# Schematic.net
KiCad netlist of a schematic drawn in EAGLE
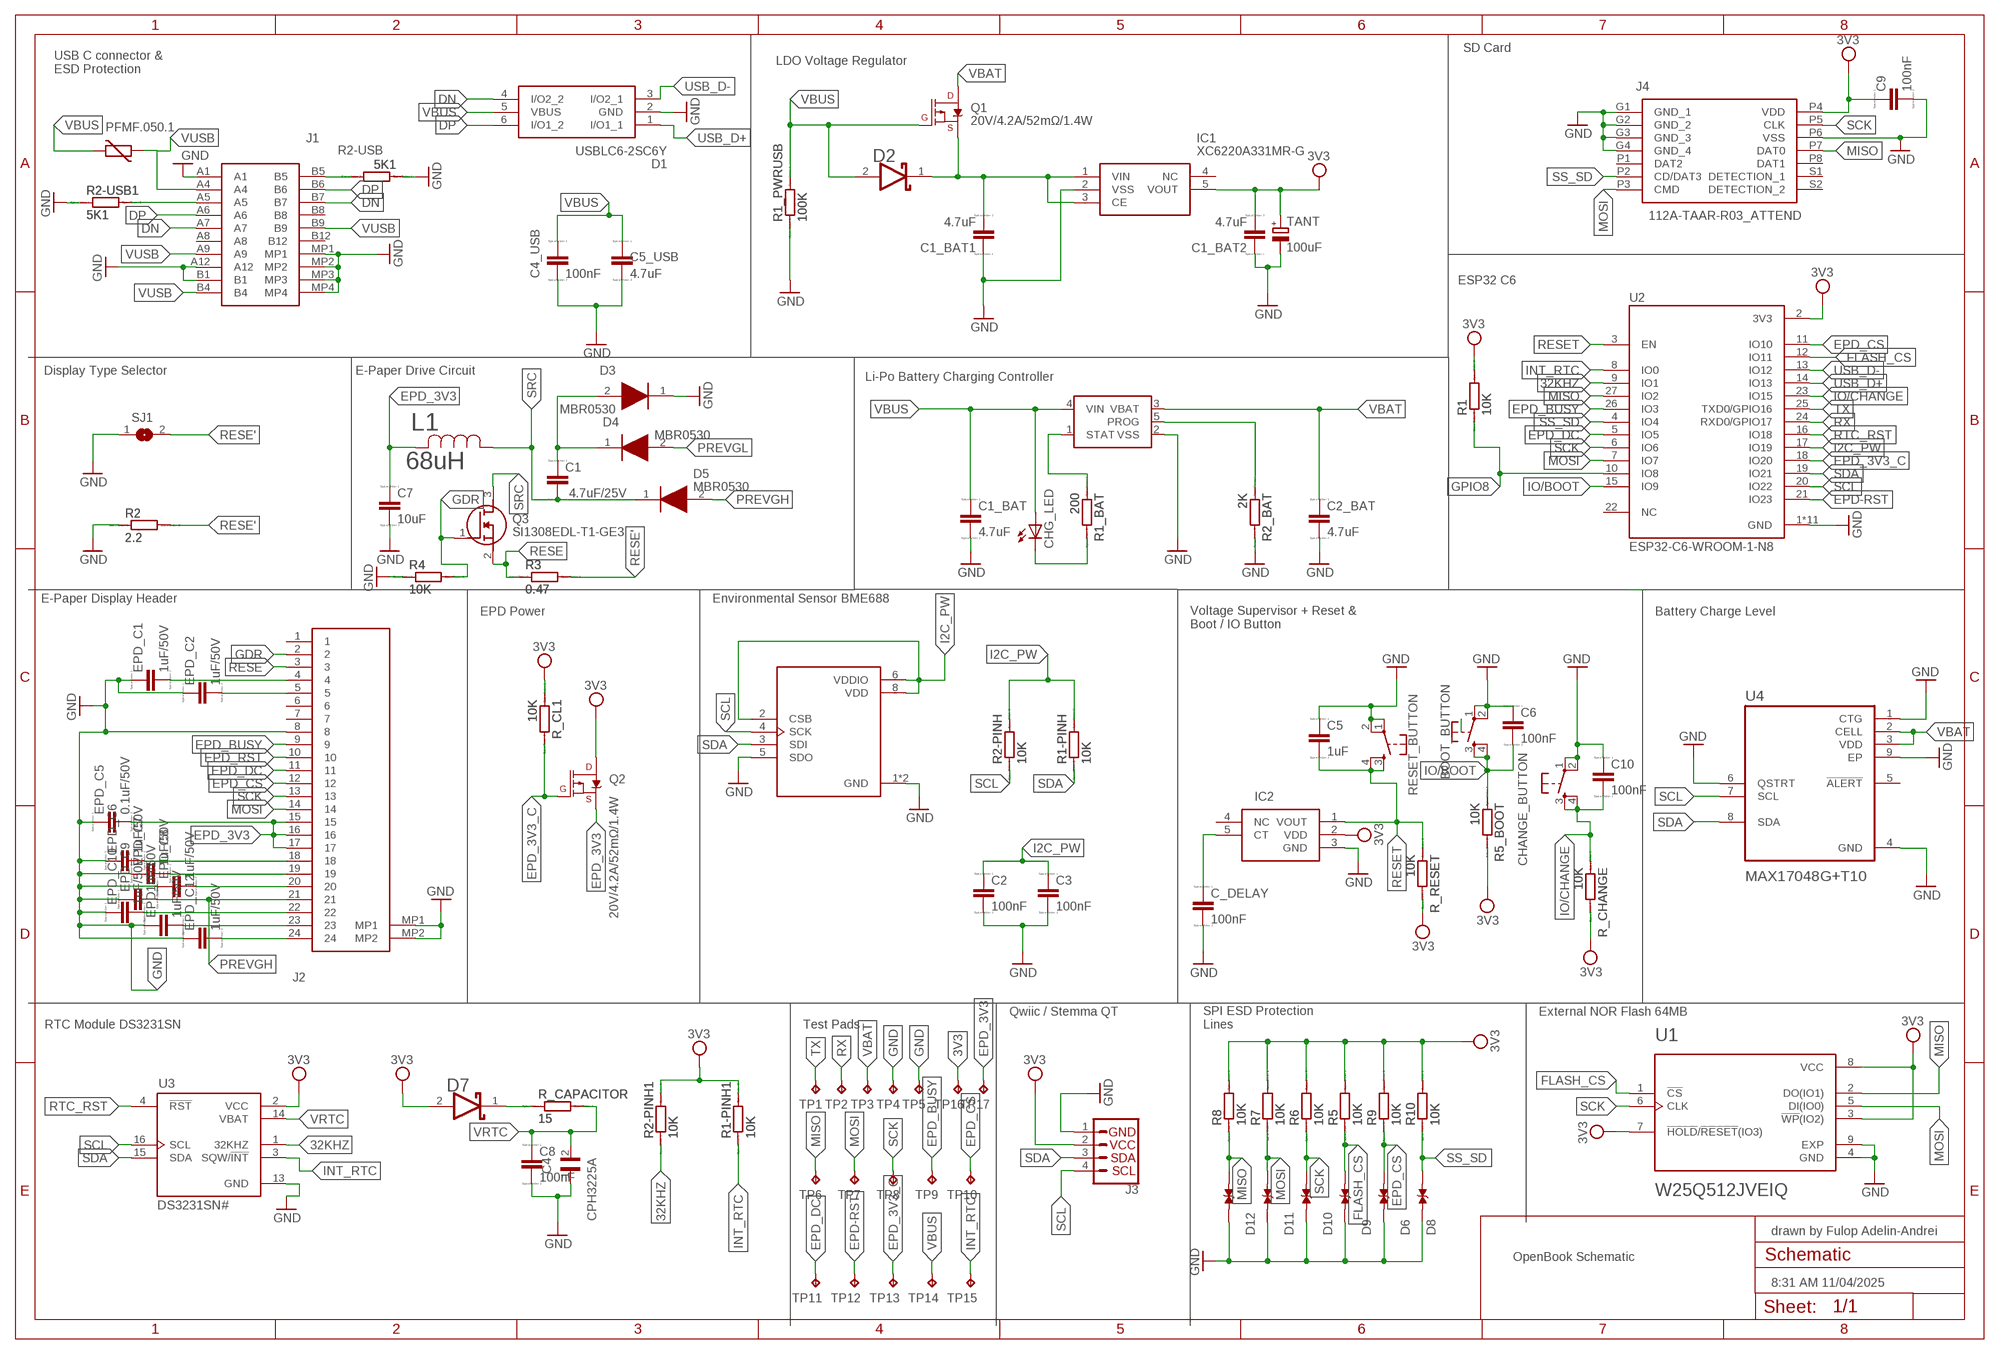
[diagram p0: schematic, sheet 1]

(export (version "E")
  (design (tool "Eeschema 10.0.6"))
  (components
    (comp (ref "BOOT_BUTTON")
      (value "BUTTON_CUSYOMV1")
      (footprint "eagle-import:MYBUTTON")
      (libsource (lib "eagle-import") (part "BUTTON_CUSYOMV1"))
    )
    (comp (ref "C1")
      (value "4.7uF/25V")
      (footprint "eagle-import:EAGLE-LTSPICE_C0402")
      (libsource (lib "eagle-import") (part "EAGLE-LTSPICE_CC0402"))
    )
    (comp (ref "C1_BAT")
      (value "4.7uF")
      (footprint "eagle-import:EAGLE-LTSPICE_C0402")
      (libsource (lib "eagle-import") (part "EAGLE-LTSPICE_CC0402"))
    )
    (comp (ref "C1_BAT1")
      (value "4.7uF")
      (footprint "eagle-import:ESP32_WROVER_EAGLE-LTSPICE_C0402")
      (libsource (lib "eagle-import") (part "ESP32_WROVER_EAGLE-LTSPICE_CC0402"))
    )
    (comp (ref "C1_BAT2")
      (value "4.7uF")
      (footprint "eagle-import:ESP32_WROVER_EAGLE-LTSPICE_C0402")
      (libsource (lib "eagle-import") (part "ESP32_WROVER_EAGLE-LTSPICE_CC0402"))
    )
    (comp (ref "C2")
      (value "100nF")
      (footprint "eagle-import:ESP32_WROVER_EAGLE-LTSPICE_C0402")
      (libsource (lib "eagle-import") (part "ESP32_WROVER_EAGLE-LTSPICE_CC0402"))
    )
    (comp (ref "C2_BAT")
      (value "4.7uF")
      (footprint "eagle-import:EAGLE-LTSPICE_C0402")
      (libsource (lib "eagle-import") (part "EAGLE-LTSPICE_CC0402"))
    )
    (comp (ref "C3")
      (value "100nF")
      (footprint "eagle-import:ESP32_WROVER_EAGLE-LTSPICE_C0402")
      (libsource (lib "eagle-import") (part "ESP32_WROVER_EAGLE-LTSPICE_CC0402"))
    )
    (comp (ref "C4")
      (value "CPH3225A")
      (footprint "eagle-import:CAPCP3225X100N")
      (fields (field (name "MF") "Seiko Instruments"))
      (libsource (lib "eagle-import") (part "CPH3225A"))
    )
    (comp (ref "C4_USB")
      (value "100nF")
      (footprint "eagle-import:EAGLE-LTSPICE_C0402")
      (libsource (lib "eagle-import") (part "EAGLE-LTSPICE_CC0402"))
    )
    (comp (ref "C5")
      (value "1uF")
      (footprint "eagle-import:ESP32_WROVER_EAGLE-LTSPICE_C0402")
      (libsource (lib "eagle-import") (part "ESP32_WROVER_EAGLE-LTSPICE_CC0402"))
    )
    (comp (ref "C5_USB")
      (value "4.7uF")
      (footprint "eagle-import:EAGLE-LTSPICE_C0402")
      (libsource (lib "eagle-import") (part "EAGLE-LTSPICE_CC0402"))
    )
    (comp (ref "C6")
      (value "100nF")
      (footprint "eagle-import:ESP32_WROVER_EAGLE-LTSPICE_C0402")
      (libsource (lib "eagle-import") (part "ESP32_WROVER_EAGLE-LTSPICE_CC0402"))
    )
    (comp (ref "C7")
      (value "10uF")
      (footprint "eagle-import:EAGLE-LTSPICE_C0402")
      (libsource (lib "eagle-import") (part "EAGLE-LTSPICE_CC0402"))
    )
    (comp (ref "C8")
      (value "100nF")
      (footprint "eagle-import:ESP32_WROVER_EAGLE-LTSPICE_C0402")
      (libsource (lib "eagle-import") (part "ESP32_WROVER_EAGLE-LTSPICE_CC0402"))
    )
    (comp (ref "C9")
      (value "100nF")
      (footprint "eagle-import:EAGLE-LTSPICE_C0402")
      (libsource (lib "eagle-import") (part "EAGLE-LTSPICE_CC0402"))
    )
    (comp (ref "C10")
      (value "100nF")
      (footprint "eagle-import:ESP32_WROVER_EAGLE-LTSPICE_C0402")
      (libsource (lib "eagle-import") (part "ESP32_WROVER_EAGLE-LTSPICE_CC0402"))
    )
    (comp (ref "CHANGE_BUTTON")
      (value "BUTTON_CUSYOMV1")
      (footprint "eagle-import:MYBUTTON")
      (libsource (lib "eagle-import") (part "BUTTON_CUSYOMV1"))
    )
    (comp (ref "CHG_LED")
      (value "ADAFRUIT_LEDCHIP-LED0603")
      (footprint "eagle-import:ADAFRUIT_CHIP-LED0603")
      (libsource (lib "eagle-import") (part "ADAFRUIT_LEDCHIP-LED0603"))
    )
    (comp (ref "C_DELAY")
      (value "100nF")
      (footprint "eagle-import:EAGLE-LTSPICE_C0402")
      (libsource (lib "eagle-import") (part "EAGLE-LTSPICE_CC0402"))
    )
    (comp (ref "D1")
      (value "USBLC6-2SC6Y")
      (footprint "eagle-import:SOT95P280X145-6N")
      (fields (field (name "MF") "STMicroelectronics"))
      (libsource (lib "eagle-import") (part "USBLC6-2SC6Y"))
    )
    (comp (ref "D2")
      (value "ESP32_WROVER_AVX---SD0805S020S1R0_AVX_SD0805S020S1R0_0_0AVX_SD0805S020S1R0_0_0")
      (footprint "eagle-import:ESP32_WROVER_AVX---SD0805S020S1R0_AVX_SD0805S020S1R0_0")
      (fields
        (field (name "DIGIKEY_PART_NUMBER") "478-7800-1-ND")
        (field (name "MF") "AVX")
        (field (name "MOUSER_PART_NUMBER") "581-SD0805S020S1R0")
      )
      (libsource (lib "eagle-import") (part "ESP32_WROVER_AVX---SD0805S020S1R0_AVX_SD0805S020S1R0_0_0AVX_SD0805S020S1R0_0_0"))
    )
    (comp (ref "D3")
      (value "MBR0530")
      (footprint "eagle-import:SOD3716X135N")
      (fields (field (name "MF") "ON Semiconductor"))
      (libsource (lib "eagle-import") (part "MBR0530"))
    )
    (comp (ref "D4")
      (value "MBR0530")
      (footprint "eagle-import:SOD3716X135N")
      (fields (field (name "MF") "ON Semiconductor"))
      (libsource (lib "eagle-import") (part "MBR0530"))
    )
    (comp (ref "D5")
      (value "MBR0530")
      (footprint "eagle-import:SOD3716X135N")
      (fields (field (name "MF") "ON Semiconductor"))
      (libsource (lib "eagle-import") (part "MBR0530"))
    )
    (comp (ref "D6")
      (value "PGB1010603MR")
      (footprint "eagle-import:DIOC1608X36N")
      (fields (field (name "MF") "Littelfuse Inc."))
      (libsource (lib "eagle-import") (part "PGB1010603MR"))
    )
    (comp (ref "D7")
      (value "ESP32_WROVER_AVX---SD0805S020S1R0_AVX_SD0805S020S1R0_0_0AVX_SD0805S020S1R0_0_0")
      (footprint "eagle-import:ESP32_WROVER_AVX---SD0805S020S1R0_AVX_SD0805S020S1R0_0")
      (fields
        (field (name "DIGIKEY_PART_NUMBER") "478-7800-1-ND")
        (field (name "MF") "AVX")
        (field (name "MOUSER_PART_NUMBER") "581-SD0805S020S1R0")
      )
      (libsource (lib "eagle-import") (part "ESP32_WROVER_AVX---SD0805S020S1R0_AVX_SD0805S020S1R0_0_0AVX_SD0805S020S1R0_0_0"))
    )
    (comp (ref "D8")
      (value "PGB1010603MR")
      (footprint "eagle-import:DIOC1608X36N")
      (fields (field (name "MF") "Littelfuse Inc."))
      (libsource (lib "eagle-import") (part "PGB1010603MR"))
    )
    (comp (ref "D9")
      (value "PGB1010603MR")
      (footprint "eagle-import:DIOC1608X36N")
      (fields (field (name "MF") "Littelfuse Inc."))
      (libsource (lib "eagle-import") (part "PGB1010603MR"))
    )
    (comp (ref "D10")
      (value "PGB1010603MR")
      (footprint "eagle-import:DIOC1608X36N")
      (fields (field (name "MF") "Littelfuse Inc."))
      (libsource (lib "eagle-import") (part "PGB1010603MR"))
    )
    (comp (ref "D11")
      (value "PGB1010603MR")
      (footprint "eagle-import:DIOC1608X36N")
      (fields (field (name "MF") "Littelfuse Inc."))
      (libsource (lib "eagle-import") (part "PGB1010603MR"))
    )
    (comp (ref "D12")
      (value "PGB1010603MR")
      (footprint "eagle-import:DIOC1608X36N")
      (fields (field (name "MF") "Littelfuse Inc."))
      (libsource (lib "eagle-import") (part "PGB1010603MR"))
    )
    (comp (ref "EPD_C1")
      (value "1uF/50V")
      (footprint "eagle-import:EAGLE-LTSPICE_C0402")
      (libsource (lib "eagle-import") (part "EAGLE-LTSPICE_CC0402"))
    )
    (comp (ref "EPD_C2")
      (value "1uF/50V")
      (footprint "eagle-import:EAGLE-LTSPICE_C0402")
      (libsource (lib "eagle-import") (part "EAGLE-LTSPICE_CC0402"))
    )
    (comp (ref "EPD_C5")
      (value "0.1uF/50V")
      (footprint "eagle-import:EAGLE-LTSPICE_C0402")
      (libsource (lib "eagle-import") (part "EAGLE-LTSPICE_CC0402"))
    )
    (comp (ref "EPD_C6")
      (value "1uF/50V")
      (footprint "eagle-import:EAGLE-LTSPICE_C0402")
      (libsource (lib "eagle-import") (part "EAGLE-LTSPICE_CC0402"))
    )
    (comp (ref "EPD_C7")
      (value "1uF/50V")
      (footprint "eagle-import:EAGLE-LTSPICE_C0402")
      (libsource (lib "eagle-import") (part "EAGLE-LTSPICE_CC0402"))
    )
    (comp (ref "EPD_C8")
      (value "1uF/50V")
      (footprint "eagle-import:EAGLE-LTSPICE_C0402")
      (libsource (lib "eagle-import") (part "EAGLE-LTSPICE_CC0402"))
    )
    (comp (ref "EPD_C9")
      (value "1uF/50V")
      (footprint "eagle-import:EAGLE-LTSPICE_C0402")
      (libsource (lib "eagle-import") (part "EAGLE-LTSPICE_CC0402"))
    )
    (comp (ref "EPD_C10")
      (value "1uF/50V")
      (footprint "eagle-import:EAGLE-LTSPICE_C0402")
      (libsource (lib "eagle-import") (part "EAGLE-LTSPICE_CC0402"))
    )
    (comp (ref "EPD_C11")
      (value "1uF/50V")
      (footprint "eagle-import:EAGLE-LTSPICE_C0402")
      (libsource (lib "eagle-import") (part "EAGLE-LTSPICE_CC0402"))
    )
    (comp (ref "EPD_C12")
      (value "1uF/50V")
      (footprint "eagle-import:EAGLE-LTSPICE_C0402")
      (libsource (lib "eagle-import") (part "EAGLE-LTSPICE_CC0402"))
    )
    (comp (ref "IC1")
      (value "XC6220A331MR-G")
      (footprint "eagle-import:SOT95P280X120-5N")
      (fields (field (name "MOUSER_PART_NUMBER") "865-XC6220A331MR-G"))
      (libsource (lib "eagle-import") (part "XC6220A331MR-G"))
    )
    (comp (ref "IC2")
      (value "BD5229G-TR")
      (footprint "eagle-import:SOT95P280X125-5N")
      (fields (field (name "MOUSER_PART_NUMBER") "755-BD5229G-TR"))
      (libsource (lib "eagle-import") (part "BD5229G-TR"))
    )
    (comp (ref "J1")
      (value "SAMACSYS_PARTS_USB4110-GF-A")
      (footprint "eagle-import:SAMACSYS_PARTS_USB4110GFA")
      (fields
        (field (name "MANUFACTURER_PART_NUMBER") "USB4110-GF-A")
        (field (name "MOUSER_PART_NUMBER") "640-USB4110-GF-A")
      )
      (libsource (lib "eagle-import") (part "SAMACSYS_PARTS_USB4110-GF-A"))
    )
    (comp (ref "J2")
      (value "FH34SRJ-24S-0.5SH_99_")
      (footprint "eagle-import:FH34SRJ24S05SH99")
      (fields
        (field (name "MANUFACTURER_PART_NUMBER") "FH34SRJ-24S-0.5SH(99)")
        (field (name "MOUSER_PART_NUMBER") "798-FH34SRJ24S05SH99")
      )
      (libsource (lib "eagle-import") (part "FH34SRJ-24S-0.5SH_99_"))
    )
    (comp (ref "J3")
      (value "QWIIC_RIGHT_ANGLE")
      (footprint "eagle-import:JST04_1MM_RA")
      (libsource (lib "eagle-import") (part "QWIIC_CONNECTORJS-1MM"))
    )
    (comp (ref "J4")
      (value "112A-TAAR-R03_ATTEND")
      (footprint "eagle-import:112ATAARR03ATTEND")
      (fields (field (name "MANUFACTURER_PART_NUMBER") "112A-TAAR-R03 ATTEND"))
      (libsource (lib "eagle-import") (part "112A-TAAR-R03_ATTEND"))
    )
    (comp (ref "L1")
      (value "68uH")
      (footprint "eagle-import:IND_4828-WE-TPC_WRE")
      (fields
        (field (name "MANUFACTURER_PART_NUMBER") "744043680")
        (field (name "COPYRIGHT") "Copyright (C) 2024 Ultra Librarian. All rights reserved.")
      )
      (libsource (lib "eagle-import") (part "744043680IND_4828-WE-TPC_WRE"))
    )
    (comp (ref "PFMF.050.1")
      (value "ESP32C6_VARISTORCN1812")
      (footprint "eagle-import:ESP32C6_VARISTOR_CT_CN1812")
      (libsource (lib "eagle-import") (part "ESP32C6_VARISTORCN1812"))
    )
    (comp (ref "Q1")
      (value "20V/4.2A/52mΩ/1.4W")
      (footprint "eagle-import:ESP32_WROVER_SPARKFUN-DISCRETESEMI_SOT23-3")
      (libsource (lib "eagle-import") (part "ESP32_WROVER_SPARKFUN-DISCRETESEMI_MOSFET_PCH-DMG2305UX-7"))
    )
    (comp (ref "Q2")
      (value "20V/4.2A/52mΩ/1.4W")
      (footprint "eagle-import:ESP32_WROVER_SPARKFUN-DISCRETESEMI_SOT23-3")
      (libsource (lib "eagle-import") (part "ESP32_WROVER_SPARKFUN-DISCRETESEMI_MOSFET_PCH-DMG2305UX-7"))
    )
    (comp (ref "Q3")
      (value "SI1308EDL-T1-GE3")
      (footprint "eagle-import:SOT65P210X110-3N")
      (fields (field (name "MF") "Vishay Siliconix"))
      (libsource (lib "eagle-import") (part "SI1308EDL-T1-GE3"))
    )
    (comp (ref "R1")
      (value "10K")
      (footprint "eagle-import:ESP32_WROVER_EAGLE-LTSPICE_R0402")
      (libsource (lib "eagle-import") (part "ESP32_WROVER_EAGLE-LTSPICE_RR0402"))
    )
    (comp (ref "R1-PINH")
      (value "10K")
      (footprint "eagle-import:ESP32_WROVER_EAGLE-LTSPICE_R0402")
      (libsource (lib "eagle-import") (part "ESP32_WROVER_EAGLE-LTSPICE_RR0402"))
    )
    (comp (ref "R1-PINH1")
      (value "10K")
      (footprint "eagle-import:ESP32_WROVER_EAGLE-LTSPICE_R0402")
      (libsource (lib "eagle-import") (part "ESP32_WROVER_EAGLE-LTSPICE_RR0402"))
    )
    (comp (ref "R1_BAT")
      (value "200")
      (footprint "eagle-import:ESP32_WROVER_EAGLE-LTSPICE_R0402")
      (libsource (lib "eagle-import") (part "ESP32_WROVER_EAGLE-LTSPICE_RR0402"))
    )
    (comp (ref "R1_PWRUSB")
      (value "100K")
      (footprint "eagle-import:ESP32_WROVER_EAGLE-LTSPICE_R0402")
      (libsource (lib "eagle-import") (part "ESP32_WROVER_EAGLE-LTSPICE_RR0402"))
    )
    (comp (ref "R2")
      (value "2.2")
      (footprint "eagle-import:ESP32_WROVER_EAGLE-LTSPICE_R0402")
      (libsource (lib "eagle-import") (part "ESP32_WROVER_EAGLE-LTSPICE_RR0402"))
    )
    (comp (ref "R2-PINH")
      (value "10K")
      (footprint "eagle-import:ESP32_WROVER_EAGLE-LTSPICE_R0402")
      (libsource (lib "eagle-import") (part "ESP32_WROVER_EAGLE-LTSPICE_RR0402"))
    )
    (comp (ref "R2-PINH1")
      (value "10K")
      (footprint "eagle-import:ESP32_WROVER_EAGLE-LTSPICE_R0402")
      (libsource (lib "eagle-import") (part "ESP32_WROVER_EAGLE-LTSPICE_RR0402"))
    )
    (comp (ref "R2-USB")
      (value "5K1")
      (footprint "eagle-import:ESP32_WROVER_EAGLE-LTSPICE_R0402")
      (libsource (lib "eagle-import") (part "ESP32_WROVER_EAGLE-LTSPICE_RR0402"))
    )
    (comp (ref "R2-USB1")
      (value "5K1")
      (footprint "eagle-import:ESP32_WROVER_EAGLE-LTSPICE_R0402")
      (libsource (lib "eagle-import") (part "ESP32_WROVER_EAGLE-LTSPICE_RR0402"))
    )
    (comp (ref "R2_BAT")
      (value "2K")
      (footprint "eagle-import:ESP32_WROVER_EAGLE-LTSPICE_R0402")
      (libsource (lib "eagle-import") (part "ESP32_WROVER_EAGLE-LTSPICE_RR0402"))
    )
    (comp (ref "R3")
      (value "0.47")
      (footprint "eagle-import:ESP32_WROVER_EAGLE-LTSPICE_R0402")
      (libsource (lib "eagle-import") (part "ESP32_WROVER_EAGLE-LTSPICE_RR0402"))
    )
    (comp (ref "R4")
      (value "10K")
      (footprint "eagle-import:ESP32_WROVER_EAGLE-LTSPICE_R0402")
      (libsource (lib "eagle-import") (part "ESP32_WROVER_EAGLE-LTSPICE_RR0402"))
    )
    (comp (ref "R5")
      (value "10K")
      (footprint "eagle-import:ESP32_WROVER_EAGLE-LTSPICE_R0402")
      (libsource (lib "eagle-import") (part "ESP32_WROVER_EAGLE-LTSPICE_RR0402"))
    )
    (comp (ref "R5_BOOT")
      (value "10K")
      (footprint "eagle-import:ESP32_WROVER_EAGLE-LTSPICE_R0402")
      (libsource (lib "eagle-import") (part "ESP32_WROVER_EAGLE-LTSPICE_RR0402"))
    )
    (comp (ref "R6")
      (value "10K")
      (footprint "eagle-import:ESP32_WROVER_EAGLE-LTSPICE_R0402")
      (libsource (lib "eagle-import") (part "ESP32_WROVER_EAGLE-LTSPICE_RR0402"))
    )
    (comp (ref "R7")
      (value "10K")
      (footprint "eagle-import:ESP32_WROVER_EAGLE-LTSPICE_R0402")
      (libsource (lib "eagle-import") (part "ESP32_WROVER_EAGLE-LTSPICE_RR0402"))
    )
    (comp (ref "R8")
      (value "10K")
      (footprint "eagle-import:ESP32_WROVER_EAGLE-LTSPICE_R0402")
      (libsource (lib "eagle-import") (part "ESP32_WROVER_EAGLE-LTSPICE_RR0402"))
    )
    (comp (ref "R9")
      (value "10K")
      (footprint "eagle-import:ESP32_WROVER_EAGLE-LTSPICE_R0402")
      (libsource (lib "eagle-import") (part "ESP32_WROVER_EAGLE-LTSPICE_RR0402"))
    )
    (comp (ref "R10")
      (value "10K")
      (footprint "eagle-import:ESP32_WROVER_EAGLE-LTSPICE_R0402")
      (libsource (lib "eagle-import") (part "ESP32_WROVER_EAGLE-LTSPICE_RR0402"))
    )
    (comp (ref "RESET_BUTTON")
      (value "BUTTON_CUSYOMV1")
      (footprint "eagle-import:MYBUTTON")
      (libsource (lib "eagle-import") (part "BUTTON_CUSYOMV1"))
    )
    (comp (ref "R_CAPACITOR")
      (value "15")
      (footprint "eagle-import:ESP32_WROVER_EAGLE-LTSPICE_R0402")
      (libsource (lib "eagle-import") (part "ESP32_WROVER_EAGLE-LTSPICE_RR0402"))
    )
    (comp (ref "R_CHANGE")
      (value "10K")
      (footprint "eagle-import:ESP32_WROVER_EAGLE-LTSPICE_R0402")
      (libsource (lib "eagle-import") (part "ESP32_WROVER_EAGLE-LTSPICE_RR0402"))
    )
    (comp (ref "R_CL1")
      (value "10K")
      (footprint "eagle-import:ESP32_WROVER_EAGLE-LTSPICE_R0402")
      (libsource (lib "eagle-import") (part "ESP32_WROVER_EAGLE-LTSPICE_RR0402"))
    )
    (comp (ref "R_RESET")
      (value "10K")
      (footprint "eagle-import:ESP32_WROVER_EAGLE-LTSPICE_R0402")
      (libsource (lib "eagle-import") (part "ESP32_WROVER_EAGLE-LTSPICE_RR0402"))
    )
    (comp (ref "SJ1") (value "SJ") (footprint "eagle-import:SJ") (libsource (lib "eagle-import") (part "SJ")))
    (comp (ref "TANT")
      (value "100uF")
      (footprint "eagle-import:RCL_CT3528")
      (libsource (lib "eagle-import") (part "RCL_CPOL-EUCT3528"))
    )
    (comp (ref "TP1")
      (value "TPTP20R")
      (footprint "eagle-import:TP20R")
      (libsource (lib "eagle-import") (part "TPTP20R"))
    )
    (comp (ref "TP2")
      (value "TPTP20R")
      (footprint "eagle-import:TP20R")
      (libsource (lib "eagle-import") (part "TPTP20R"))
    )
    (comp (ref "TP3")
      (value "TPTP20R")
      (footprint "eagle-import:TP20R")
      (libsource (lib "eagle-import") (part "TPTP20R"))
    )
    (comp (ref "TP4")
      (value "TPTP20R")
      (footprint "eagle-import:TP20R")
      (libsource (lib "eagle-import") (part "TPTP20R"))
    )
    (comp (ref "TP5")
      (value "TPTP20R")
      (footprint "eagle-import:TP20R")
      (libsource (lib "eagle-import") (part "TPTP20R"))
    )
    (comp (ref "TP6")
      (value "TPTP20R")
      (footprint "eagle-import:TP20R")
      (libsource (lib "eagle-import") (part "TPTP20R"))
    )
    (comp (ref "TP7")
      (value "TPTP20R")
      (footprint "eagle-import:TP20R")
      (libsource (lib "eagle-import") (part "TPTP20R"))
    )
    (comp (ref "TP8")
      (value "TPTP20R")
      (footprint "eagle-import:TP20R")
      (libsource (lib "eagle-import") (part "TPTP20R"))
    )
    (comp (ref "TP9")
      (value "TPTP20R")
      (footprint "eagle-import:TP20R")
      (libsource (lib "eagle-import") (part "TPTP20R"))
    )
    (comp (ref "TP10")
      (value "TPTP20R")
      (footprint "eagle-import:TP20R")
      (libsource (lib "eagle-import") (part "TPTP20R"))
    )
    (comp (ref "TP11")
      (value "TPTP20R")
      (footprint "eagle-import:TP20R")
      (libsource (lib "eagle-import") (part "TPTP20R"))
    )
    (comp (ref "TP12")
      (value "TPTP20R")
      (footprint "eagle-import:TP20R")
      (libsource (lib "eagle-import") (part "TPTP20R"))
    )
    (comp (ref "TP13")
      (value "TPTP20R")
      (footprint "eagle-import:TP20R")
      (libsource (lib "eagle-import") (part "TPTP20R"))
    )
    (comp (ref "TP14")
      (value "TPTP20R")
      (footprint "eagle-import:TP20R")
      (libsource (lib "eagle-import") (part "TPTP20R"))
    )
    (comp (ref "TP15")
      (value "TPTP20R")
      (footprint "eagle-import:TP20R")
      (libsource (lib "eagle-import") (part "TPTP20R"))
    )
    (comp (ref "TP16")
      (value "TPTP20R")
      (footprint "eagle-import:TP20R")
      (libsource (lib "eagle-import") (part "TPTP20R"))
    )
    (comp (ref "TP17")
      (value "TPTP20R")
      (footprint "eagle-import:TP20R")
      (libsource (lib "eagle-import") (part "TPTP20R"))
    )
    (comp (ref "U1")
      (value "W25Q512JVEIQ")
      (footprint "eagle-import:SON127P600X800X80-9N")
      (fields (field (name "MF") "Winbond Electronics"))
      (libsource (lib "eagle-import") (part "W25Q512JVEIQ"))
    )
    (comp (ref "U2")
      (value "ESP32-C6-WROOM-1-N8")
      (footprint "eagle-import:XCVR_ESP32-C6-WROOM-1-N8")
      (fields (field (name "MF") "Espressif Systems"))
      (libsource (lib "eagle-import") (part "ESP32-C6-WROOM-1-N8"))
    )
    (comp (ref "U3")
      (value "DS3231SN#")
      (footprint "eagle-import:SOIC127P1032X265-16N")
      (fields (field (name "MF") "Analog Devices"))
      (libsource (lib "eagle-import") (part "DS3231SN#"))
    )
    (comp (ref "U4")
      (value "MAX17048G+T10")
      (footprint "eagle-import:SON50P200X200X80-9N")
      (fields (field (name "MF") "Analog Devices"))
      (libsource (lib "eagle-import") (part "MAX17048G+T10"))
    )
    (comp (ref "U9")
      (value "ESP32_WROVER_SPARKFUN-IC-POWER_MCP73831")
      (footprint "eagle-import:ESP32_WROVER_SPARKFUN-IC-POWER_SOT23-5")
      (libsource (lib "eagle-import") (part "ESP32_WROVER_SPARKFUN-IC-POWER_MCP73831"))
    )
    (comp (ref "U10")
      (value "ESP32_WROVER_BME680_BME680")
      (footprint "eagle-import:ESP32_WROVER_BME680_PSON80P300X300X100-8N")
      (fields (field (name "MF") "Bosch Sensortec") (field (name "MP") "BME680"))
      (libsource (lib "eagle-import") (part "ESP32_WROVER_BME680_BME680"))
    )
  )
  (nets
    (net (code "1") (name "3V3") (class "Default")
      (node (ref "C1_BAT2") (pin "2") (pinfunction "2_2") (pintype "passive"))
      (node (ref "C9") (pin "1") (pinfunction "1_1") (pintype "passive"))
      (node (ref "D7") (pin "2") (pinfunction "ANODE_2") (pintype "bidirectional"))
      (node (ref "IC1") (pin "5") (pinfunction "VOUT_5") (pintype "bidirectional"))
      (node (ref "IC2") (pin "2") (pinfunction "VDD_2") (pintype "bidirectional"))
      (node (ref "J3") (pin "2") (pinfunction "2_2") (pintype "power_in"))
      (node (ref "J4") (pin "P4") (pinfunction "VDD_P4") (pintype "bidirectional"))
      (node (ref "Q2") (pin "3") (pinfunction "D_3") (pintype "bidirectional"))
      (node (ref "R1") (pin "2") (pinfunction "2_2") (pintype "passive"))
      (node (ref "R1-PINH1") (pin "2") (pinfunction "2_2") (pintype "passive"))
      (node (ref "R10") (pin "2") (pinfunction "2_2") (pintype "passive"))
      (node (ref "R2-PINH1") (pin "2") (pinfunction "2_2") (pintype "passive"))
      (node (ref "R5") (pin "2") (pinfunction "2_2") (pintype "passive"))
      (node (ref "R5_BOOT") (pin "2") (pinfunction "2_2") (pintype "passive"))
      (node (ref "R6") (pin "2") (pinfunction "2_2") (pintype "passive"))
      (node (ref "R7") (pin "2") (pinfunction "2_2") (pintype "passive"))
      (node (ref "R8") (pin "2") (pinfunction "2_2") (pintype "passive"))
      (node (ref "R9") (pin "2") (pinfunction "2_2") (pintype "passive"))
      (node (ref "R_CHANGE") (pin "2") (pinfunction "2_2") (pintype "passive"))
      (node (ref "R_CL1") (pin "1") (pinfunction "1_1") (pintype "passive"))
      (node (ref "R_RESET") (pin "2") (pinfunction "2_2") (pintype "passive"))
      (node (ref "TANT") (pin "+") (pinfunction "+_+") (pintype "passive"))
      (node (ref "TP16") (pin "TP") (pinfunction "TP_TP") (pintype "input"))
      (node (ref "U1") (pin "3") (pinfunction "~{WP}(IO2)_3") (pintype "bidirectional"))
      (node (ref "U1") (pin "7") (pinfunction "~{HOLD}/~{RESET}(IO3)_7") (pintype "bidirectional"))
      (node (ref "U1") (pin "8") (pinfunction "VCC_8") (pintype "power_in"))
      (node (ref "U2") (pin "2") (pinfunction "3V3_2") (pintype "power_in"))
      (node (ref "U3") (pin "2") (pinfunction "VCC_2") (pintype "power_in"))
    )
    (net (code "2") (name "32KHZ") (class "Default")
      (node (ref "R2-PINH1") (pin "1") (pinfunction "1_1") (pintype "passive"))
      (node (ref "U2") (pin "9") (pinfunction "IO1_9") (pintype "bidirectional"))
      (node (ref "U3") (pin "1") (pinfunction "32KHZ_1") (pintype "output"))
    )
    (net (code "3") (name "DN") (class "Default")
      (node (ref "D1") (pin "4") (pinfunction "I/O2_2_4") (pintype "bidirectional"))
      (node (ref "J1") (pin "A7") (pinfunction "A7_A7") (pintype "bidirectional"))
      (node (ref "J1") (pin "B7") (pinfunction "B7_B7") (pintype "bidirectional"))
    )
    (net (code "4") (name "DP") (class "Default")
      (node (ref "D1") (pin "6") (pinfunction "I/O1_2_6") (pintype "bidirectional"))
      (node (ref "J1") (pin "A6") (pinfunction "A6_A6") (pintype "bidirectional"))
      (node (ref "J1") (pin "B6") (pinfunction "B6_B6") (pintype "bidirectional"))
    )
    (net (code "5") (name "EPD-RST") (class "Default")
      (node (ref "TP12") (pin "TP") (pinfunction "TP_TP") (pintype "input"))
      (node (ref "U2") (pin "21") (pinfunction "IO23_21") (pintype "bidirectional"))
    )
    (net (code "6") (name "EPD_3V3") (class "Default")
      (node (ref "C7") (pin "1") (pinfunction "1_1") (pintype "passive"))
      (node (ref "EPD_C5") (pin "2") (pinfunction "2_2") (pintype "passive"))
      (node (ref "J2") (pin "15") (pinfunction "15_15") (pintype "bidirectional"))
      (node (ref "J2") (pin "16") (pinfunction "16_16") (pintype "bidirectional"))
      (node (ref "J2") (pin "17") (pinfunction "17_17") (pintype "bidirectional"))
      (node (ref "L1") (pin "2") (pinfunction "2_2") (pintype "passive"))
      (node (ref "Q2") (pin "2") (pinfunction "S_2") (pintype "bidirectional"))
      (node (ref "TP17") (pin "TP") (pinfunction "TP_TP") (pintype "input"))
    )
    (net (code "7") (name "EPD_3V3_C") (class "Default")
      (node (ref "Q2") (pin "1") (pinfunction "G_1") (pintype "bidirectional"))
      (node (ref "R_CL1") (pin "2") (pinfunction "2_2") (pintype "passive"))
      (node (ref "TP13") (pin "TP") (pinfunction "TP_TP") (pintype "input"))
      (node (ref "U2") (pin "18") (pinfunction "IO20_18") (pintype "bidirectional"))
    )
    (net (code "8") (name "EPD_BUSY") (class "Default")
      (node (ref "J2") (pin "9") (pinfunction "9_9") (pintype "bidirectional"))
      (node (ref "TP9") (pin "TP") (pinfunction "TP_TP") (pintype "input"))
      (node (ref "U2") (pin "26") (pinfunction "IO3_26") (pintype "bidirectional"))
    )
    (net (code "9") (name "EPD_CS") (class "Default")
      (node (ref "D6") (pin "2") (pinfunction "2_2") (pintype "passive"))
      (node (ref "J2") (pin "12") (pinfunction "12_12") (pintype "bidirectional"))
      (node (ref "R9") (pin "1") (pinfunction "1_1") (pintype "passive"))
      (node (ref "TP10") (pin "TP") (pinfunction "TP_TP") (pintype "input"))
      (node (ref "U2") (pin "11") (pinfunction "IO10_11") (pintype "bidirectional"))
    )
    (net (code "10") (name "EPD_DC") (class "Default")
      (node (ref "J2") (pin "11") (pinfunction "11_11") (pintype "bidirectional"))
      (node (ref "TP11") (pin "TP") (pinfunction "TP_TP") (pintype "input"))
      (node (ref "U2") (pin "5") (pinfunction "IO5_5") (pintype "bidirectional"))
    )
    (net (code "11") (name "EPD_RST") (class "Default")
      (node (ref "J2") (pin "10") (pinfunction "10_10") (pintype "bidirectional"))
    )
    (net (code "12") (name "FLASH_CS") (class "Default")
      (node (ref "D9") (pin "2") (pinfunction "2_2") (pintype "passive"))
      (node (ref "R5") (pin "1") (pinfunction "1_1") (pintype "passive"))
      (node (ref "U1") (pin "1") (pinfunction "~{CS}_1") (pintype "input"))
      (node (ref "U2") (pin "12") (pinfunction "IO11_12") (pintype "bidirectional"))
    )
    (net (code "13") (name "GDR") (class "Default")
      (node (ref "J2") (pin "2") (pinfunction "2_2") (pintype "bidirectional"))
      (node (ref "Q3") (pin "1") (pinfunction "G_1") (pintype "bidirectional"))
      (node (ref "R4") (pin "2") (pinfunction "2_2") (pintype "passive"))
    )
    (net (code "14") (name "GND") (class "Default")
      (node (ref "BOOT_BUTTON") (pin "1") (pinfunction "1_1") (pintype "passive"))
      (node (ref "BOOT_BUTTON") (pin "2") (pinfunction "2_2") (pintype "passive"))
      (node (ref "C10") (pin "1") (pinfunction "1_1") (pintype "passive"))
      (node (ref "C1_BAT") (pin "2") (pinfunction "2_2") (pintype "passive"))
      (node (ref "C1_BAT1") (pin "1") (pinfunction "1_1") (pintype "passive"))
      (node (ref "C1_BAT2") (pin "1") (pinfunction "1_1") (pintype "passive"))
      (node (ref "C2") (pin "2") (pinfunction "2_2") (pintype "passive"))
      (node (ref "C2_BAT") (pin "2") (pinfunction "2_2") (pintype "passive"))
      (node (ref "C3") (pin "2") (pinfunction "2_2") (pintype "passive"))
      (node (ref "C4") (pin "1") (pinfunction "1_1") (pintype "passive"))
      (node (ref "C4_USB") (pin "2") (pinfunction "2_2") (pintype "passive"))
      (node (ref "C5") (pin "1") (pinfunction "1_1") (pintype "passive"))
      (node (ref "C5_USB") (pin "2") (pinfunction "2_2") (pintype "passive"))
      (node (ref "C6") (pin "1") (pinfunction "1_1") (pintype "passive"))
      (node (ref "C7") (pin "2") (pinfunction "2_2") (pintype "passive"))
      (node (ref "C8") (pin "2") (pinfunction "2_2") (pintype "passive"))
      (node (ref "C9") (pin "2") (pinfunction "2_2") (pintype "passive"))
      (node (ref "CHANGE_BUTTON") (pin "1") (pinfunction "1_1") (pintype "passive"))
      (node (ref "CHANGE_BUTTON") (pin "2") (pinfunction "2_2") (pintype "passive"))
      (node (ref "C_DELAY") (pin "2") (pinfunction "2_2") (pintype "passive"))
      (node (ref "D1") (pin "2") (pinfunction "GND_2") (pintype "bidirectional"))
      (node (ref "D10") (pin "1") (pinfunction "1_1") (pintype "passive"))
      (node (ref "D11") (pin "1") (pinfunction "1_1") (pintype "passive"))
      (node (ref "D12") (pin "1") (pinfunction "1_1") (pintype "passive"))
      (node (ref "D3") (pin "1") (pinfunction "K_1") (pintype "bidirectional"))
      (node (ref "D6") (pin "1") (pinfunction "1_1") (pintype "passive"))
      (node (ref "D8") (pin "1") (pinfunction "1_1") (pintype "passive"))
      (node (ref "D9") (pin "1") (pinfunction "1_1") (pintype "passive"))
      (node (ref "EPD_C1") (pin "1") (pinfunction "1_1") (pintype "passive"))
      (node (ref "EPD_C10") (pin "1") (pinfunction "1_1") (pintype "passive"))
      (node (ref "EPD_C11") (pin "1") (pinfunction "1_1") (pintype "passive"))
      (node (ref "EPD_C12") (pin "1") (pinfunction "1_1") (pintype "passive"))
      (node (ref "EPD_C2") (pin "1") (pinfunction "1_1") (pintype "passive"))
      (node (ref "EPD_C5") (pin "1") (pinfunction "1_1") (pintype "passive"))
      (node (ref "EPD_C6") (pin "1") (pinfunction "1_1") (pintype "passive"))
      (node (ref "EPD_C7") (pin "1") (pinfunction "1_1") (pintype "passive"))
      (node (ref "EPD_C8") (pin "1") (pinfunction "1_1") (pintype "passive"))
      (node (ref "EPD_C9") (pin "1") (pinfunction "1_1") (pintype "passive"))
      (node (ref "IC1") (pin "2") (pinfunction "VSS_2") (pintype "bidirectional"))
      (node (ref "IC2") (pin "3") (pinfunction "GND_3") (pintype "bidirectional"))
      (node (ref "J1") (pin "A1") (pinfunction "A1_A1") (pintype "bidirectional"))
      (node (ref "J1") (pin "A12") (pinfunction "A12_A12") (pintype "bidirectional"))
      (node (ref "J1") (pin "B1") (pinfunction "B1_B1") (pintype "bidirectional"))
      (node (ref "J1") (pin "MP1") (pinfunction "MP1_MP1") (pintype "bidirectional"))
      (node (ref "J1") (pin "MP2") (pinfunction "MP2_MP2") (pintype "bidirectional"))
      (node (ref "J1") (pin "MP3") (pinfunction "MP3_MP3") (pintype "bidirectional"))
      (node (ref "J1") (pin "MP4") (pinfunction "MP4_MP4") (pintype "bidirectional"))
      (node (ref "J2") (pin "8") (pinfunction "8_8") (pintype "bidirectional"))
      (node (ref "J2") (pin "MP1") (pinfunction "MP1_MP1") (pintype "bidirectional"))
      (node (ref "J2") (pin "MP2") (pinfunction "MP2_MP2") (pintype "bidirectional"))
      (node (ref "J3") (pin "1") (pinfunction "1_1") (pintype "power_in"))
      (node (ref "J4") (pin "G1") (pinfunction "GND_1_G1") (pintype "bidirectional"))
      (node (ref "J4") (pin "G2") (pinfunction "GND_2_G2") (pintype "bidirectional"))
      (node (ref "J4") (pin "G3") (pinfunction "GND_3_G3") (pintype "bidirectional"))
      (node (ref "J4") (pin "G4") (pinfunction "GND_4_G4") (pintype "bidirectional"))
      (node (ref "J4") (pin "P6") (pinfunction "VSS_P6") (pintype "bidirectional"))
      (node (ref "R1_PWRUSB") (pin "1") (pinfunction "1_1") (pintype "passive"))
      (node (ref "R2") (pin "1") (pinfunction "1_1") (pintype "passive"))
      (node (ref "R2-USB") (pin "1") (pinfunction "1_1") (pintype "passive"))
      (node (ref "R2-USB1") (pin "1") (pinfunction "1_1") (pintype "passive"))
      (node (ref "R2_BAT") (pin "2") (pinfunction "2_2") (pintype "passive"))
      (node (ref "R4") (pin "1") (pinfunction "1_1") (pintype "passive"))
      (node (ref "RESET_BUTTON") (pin "1") (pinfunction "1_1") (pintype "passive"))
      (node (ref "RESET_BUTTON") (pin "2") (pinfunction "2_2") (pintype "passive"))
      (node (ref "SJ1") (pin "1") (pinfunction "1_1") (pintype "passive"))
      (node (ref "TANT") (pin "-") (pinfunction "-_-") (pintype "passive"))
      (node (ref "TP4") (pin "TP") (pinfunction "TP_TP") (pintype "input"))
      (node (ref "TP5") (pin "TP") (pinfunction "TP_TP") (pintype "input"))
      (node (ref "U1") (pin "4") (pinfunction "GND_4") (pintype "power_in"))
      (node (ref "U1") (pin "9") (pinfunction "EXP_9") (pintype "passive"))
      (node (ref "U10") (pin "1") (pinfunction "GND_1") (pintype "power_in"))
      (node (ref "U10") (pin "5") (pinfunction "SDO_5") (pintype "bidirectional"))
      (node (ref "U10") (pin "7") (pinfunction "GND_7") (pintype "power_in"))
      (node (ref "U2") (pin "1") (pinfunction "GND_1") (pintype "power_in"))
      (node (ref "U2") (pin "28") (pinfunction "GND_28") (pintype "power_in"))
      (node (ref "U2") (pin "29_1") (pinfunction "GND_29_1") (pintype "power_in"))
      (node (ref "U2") (pin "29_2") (pinfunction "GND_29_2") (pintype "power_in"))
      (node (ref "U2") (pin "29_3") (pinfunction "GND_29_3") (pintype "power_in"))
      (node (ref "U2") (pin "29_4") (pinfunction "GND_29_4") (pintype "power_in"))
      (node (ref "U2") (pin "29_5") (pinfunction "GND_29_5") (pintype "power_in"))
      (node (ref "U2") (pin "29_6") (pinfunction "GND_29_6") (pintype "power_in"))
      (node (ref "U2") (pin "29_7") (pinfunction "GND_29_7") (pintype "power_in"))
      (node (ref "U2") (pin "29_8") (pinfunction "GND_29_8") (pintype "power_in"))
      (node (ref "U2") (pin "29_9") (pinfunction "GND_29_9") (pintype "power_in"))
      (node (ref "U3") (pin "13") (pinfunction "GND_13") (pintype "power_in"))
      (node (ref "U4") (pin "1") (pinfunction "CTG_1") (pintype "power_in"))
      (node (ref "U4") (pin "4") (pinfunction "GND_4") (pintype "power_in"))
      (node (ref "U4") (pin "6") (pinfunction "QSTRT_6") (pintype "input"))
      (node (ref "U4") (pin "9") (pinfunction "EP_9") (pintype "power_in"))
      (node (ref "U9") (pin "2") (pinfunction "VSS_2") (pintype "power_in"))
    )
    (net (code "15") (name "GPIO8") (class "Default")
      (node (ref "R1") (pin "1") (pinfunction "1_1") (pintype "passive"))
      (node (ref "U2") (pin "10") (pinfunction "IO8_10") (pintype "bidirectional"))
    )
    (net (code "16") (name "I2C_PW") (class "Default")
      (node (ref "C2") (pin "1") (pinfunction "1_1") (pintype "passive"))
      (node (ref "C3") (pin "1") (pinfunction "1_1") (pintype "passive"))
      (node (ref "R1-PINH") (pin "2") (pinfunction "2_2") (pintype "passive"))
      (node (ref "R2-PINH") (pin "2") (pinfunction "2_2") (pintype "passive"))
      (node (ref "U10") (pin "2") (pinfunction "CSB_2") (pintype "input"))
      (node (ref "U10") (pin "6") (pinfunction "VDDIO_6") (pintype "power_in"))
      (node (ref "U10") (pin "8") (pinfunction "VDD_8") (pintype "power_in"))
      (node (ref "U2") (pin "17") (pinfunction "IO19_17") (pintype "bidirectional"))
    )
    (net (code "17") (name "INT_RTC") (class "Default")
      (node (ref "R1-PINH1") (pin "1") (pinfunction "1_1") (pintype "passive"))
      (node (ref "TP15") (pin "TP") (pinfunction "TP_TP") (pintype "input"))
      (node (ref "U2") (pin "8") (pinfunction "IO0_8") (pintype "bidirectional"))
      (node (ref "U3") (pin "3") (pinfunction "SQW/~{INT}_3") (pintype "output"))
    )
    (net (code "18") (name "IO{slash}BOOT") (class "Default")
      (node (ref "BOOT_BUTTON") (pin "3") (pinfunction "3_3") (pintype "passive"))
      (node (ref "BOOT_BUTTON") (pin "4") (pinfunction "4_4") (pintype "passive"))
      (node (ref "C6") (pin "2") (pinfunction "2_2") (pintype "passive"))
      (node (ref "R5_BOOT") (pin "1") (pinfunction "1_1") (pintype "passive"))
      (node (ref "U2") (pin "15") (pinfunction "IO9_15") (pintype "bidirectional"))
    )
    (net (code "19") (name "IO{slash}CHANGE") (class "Default")
      (node (ref "C10") (pin "2") (pinfunction "2_2") (pintype "passive"))
      (node (ref "CHANGE_BUTTON") (pin "3") (pinfunction "3_3") (pintype "passive"))
      (node (ref "CHANGE_BUTTON") (pin "4") (pinfunction "4_4") (pintype "passive"))
      (node (ref "R_CHANGE") (pin "1") (pinfunction "1_1") (pintype "passive"))
      (node (ref "U2") (pin "23") (pinfunction "IO15_23") (pintype "bidirectional"))
    )
    (net (code "20") (name "MISO") (class "Default")
      (node (ref "D12") (pin "2") (pinfunction "2_2") (pintype "passive"))
      (node (ref "J4") (pin "P7") (pinfunction "DAT0_P7") (pintype "bidirectional"))
      (node (ref "R8") (pin "1") (pinfunction "1_1") (pintype "passive"))
      (node (ref "TP6") (pin "TP") (pinfunction "TP_TP") (pintype "input"))
      (node (ref "U1") (pin "2") (pinfunction "DO(IO1)_2") (pintype "bidirectional"))
      (node (ref "U2") (pin "27") (pinfunction "IO2_27") (pintype "bidirectional"))
    )
    (net (code "21") (name "MOSI") (class "Default")
      (node (ref "D11") (pin "2") (pinfunction "2_2") (pintype "passive"))
      (node (ref "J2") (pin "14") (pinfunction "14_14") (pintype "bidirectional"))
      (node (ref "J4") (pin "P3") (pinfunction "CMD_P3") (pintype "bidirectional"))
      (node (ref "R7") (pin "1") (pinfunction "1_1") (pintype "passive"))
      (node (ref "TP7") (pin "TP") (pinfunction "TP_TP") (pintype "input"))
      (node (ref "U1") (pin "5") (pinfunction "DI(IO0)_5") (pintype "bidirectional"))
      (node (ref "U2") (pin "7") (pinfunction "IO7_7") (pintype "bidirectional"))
    )
    (net (code "22") (name "Net-(CHG_LED-PadC)") (class "Default")
      (node (ref "CHG_LED") (pin "C") (pinfunction "C_C") (pintype "passive"))
      (node (ref "R1_BAT") (pin "2") (pinfunction "2_2") (pintype "passive"))
    )
    (net (code "23") (name "Net-(D2-CATHODE)") (class "Default")
      (node (ref "C1_BAT1") (pin "2") (pinfunction "2_2") (pintype "passive"))
      (node (ref "D2") (pin "1") (pinfunction "CATHODE_1") (pintype "bidirectional"))
      (node (ref "IC1") (pin "1") (pinfunction "VIN_1") (pintype "bidirectional"))
      (node (ref "IC1") (pin "3") (pinfunction "CE_3") (pintype "bidirectional"))
      (node (ref "Q1") (pin "2") (pinfunction "S_2") (pintype "bidirectional"))
    )
    (net (code "24") (name "Net-(D3-A)") (class "Default")
      (node (ref "C1") (pin "1") (pinfunction "1_1") (pintype "passive"))
      (node (ref "D3") (pin "2") (pinfunction "A_2") (pintype "bidirectional"))
      (node (ref "D4") (pin "1") (pinfunction "K_1") (pintype "bidirectional"))
    )
    (net (code "25") (name "Net-(D7-CATHODE)") (class "Default")
      (node (ref "D7") (pin "1") (pinfunction "CATHODE_1") (pintype "bidirectional"))
      (node (ref "R_CAPACITOR") (pin "1") (pinfunction "1_1") (pintype "passive"))
    )
    (net (code "26") (name "Net-(EPD_C1-Pad2)") (class "Default")
      (node (ref "EPD_C1") (pin "2") (pinfunction "2_2") (pintype "passive"))
      (node (ref "J2") (pin "4") (pinfunction "4_4") (pintype "bidirectional"))
    )
    (net (code "27") (name "Net-(EPD_C2-Pad2)") (class "Default")
      (node (ref "EPD_C2") (pin "2") (pinfunction "2_2") (pintype "passive"))
      (node (ref "J2") (pin "5") (pinfunction "5_5") (pintype "bidirectional"))
    )
    (net (code "28") (name "Net-(EPD_C6-Pad2)") (class "Default")
      (node (ref "EPD_C6") (pin "2") (pinfunction "2_2") (pintype "passive"))
      (node (ref "J2") (pin "18") (pinfunction "18_18") (pintype "bidirectional"))
    )
    (net (code "29") (name "Net-(EPD_C7-Pad2)") (class "Default")
      (node (ref "EPD_C7") (pin "2") (pinfunction "2_2") (pintype "passive"))
      (node (ref "J2") (pin "19") (pinfunction "19_19") (pintype "bidirectional"))
    )
    (net (code "30") (name "Net-(EPD_C8-Pad2)") (class "Default")
      (node (ref "EPD_C8") (pin "2") (pinfunction "2_2") (pintype "passive"))
      (node (ref "J2") (pin "20") (pinfunction "20_20") (pintype "bidirectional"))
    )
    (net (code "31") (name "Net-(EPD_C10-Pad2)") (class "Default")
      (node (ref "EPD_C10") (pin "2") (pinfunction "2_2") (pintype "passive"))
      (node (ref "J2") (pin "22") (pinfunction "22_22") (pintype "bidirectional"))
    )
    (net (code "32") (name "Net-(EPD_C11-Pad2)") (class "Default")
      (node (ref "EPD_C11") (pin "2") (pinfunction "2_2") (pintype "passive"))
      (node (ref "J2") (pin "23") (pinfunction "23_23") (pintype "bidirectional"))
    )
    (net (code "33") (name "Net-(EPD_C12-Pad2)") (class "Default")
      (node (ref "EPD_C12") (pin "2") (pinfunction "2_2") (pintype "passive"))
      (node (ref "J2") (pin "24") (pinfunction "24_24") (pintype "bidirectional"))
    )
    (net (code "34") (name "Net-(IC2-CT)") (class "Default")
      (node (ref "C_DELAY") (pin "1") (pinfunction "1_1") (pintype "passive"))
      (node (ref "IC2") (pin "5") (pinfunction "CT_5") (pintype "bidirectional"))
    )
    (net (code "35") (name "Net-(J1-PadA5)") (class "Default")
      (node (ref "J1") (pin "A5") (pinfunction "A5_A5") (pintype "bidirectional"))
      (node (ref "R2-USB1") (pin "2") (pinfunction "2_2") (pintype "passive"))
    )
    (net (code "36") (name "Net-(J1-PadB5)") (class "Default")
      (node (ref "J1") (pin "B5") (pinfunction "B5_B5") (pintype "bidirectional"))
      (node (ref "R2-USB") (pin "2") (pinfunction "2_2") (pintype "passive"))
    )
    (net (code "37") (name "Net-(U9-PROG)") (class "Default")
      (node (ref "R2_BAT") (pin "1") (pinfunction "1_1") (pintype "passive"))
      (node (ref "U9") (pin "5") (pinfunction "PROG_5") (pintype "input"))
    )
    (net (code "38") (name "Net-(U9-STAT)") (class "Default")
      (node (ref "R1_BAT") (pin "1") (pinfunction "1_1") (pintype "passive"))
      (node (ref "U9") (pin "1") (pinfunction "STAT_1") (pintype "output"))
    )
    (net (code "39") (name "PREVGH") (class "Default")
      (node (ref "D5") (pin "2") (pinfunction "A_2") (pintype "bidirectional"))
      (node (ref "EPD_C9") (pin "2") (pinfunction "2_2") (pintype "passive"))
      (node (ref "J2") (pin "21") (pinfunction "21_21") (pintype "bidirectional"))
    )
    (net (code "40") (name "PREVGL") (class "Default")
      (node (ref "D4") (pin "2") (pinfunction "A_2") (pintype "bidirectional"))
    )
    (net (code "41") (name "RESE") (class "Default")
      (node (ref "J2") (pin "3") (pinfunction "3_3") (pintype "bidirectional"))
      (node (ref "Q3") (pin "2") (pinfunction "S_2") (pintype "bidirectional"))
      (node (ref "R3") (pin "1") (pinfunction "1_1") (pintype "passive"))
    )
    (net (code "42") (name "RESE'") (class "Default")
      (node (ref "R2") (pin "2") (pinfunction "2_2") (pintype "passive"))
      (node (ref "R3") (pin "2") (pinfunction "2_2") (pintype "passive"))
      (node (ref "SJ1") (pin "2") (pinfunction "2_2") (pintype "passive"))
    )
    (net (code "43") (name "RESET") (class "Default")
      (node (ref "C5") (pin "2") (pinfunction "2_2") (pintype "passive"))
      (node (ref "IC2") (pin "1") (pinfunction "VOUT_1") (pintype "bidirectional"))
      (node (ref "RESET_BUTTON") (pin "3") (pinfunction "3_3") (pintype "passive"))
      (node (ref "RESET_BUTTON") (pin "4") (pinfunction "4_4") (pintype "passive"))
      (node (ref "R_RESET") (pin "1") (pinfunction "1_1") (pintype "passive"))
      (node (ref "U2") (pin "3") (pinfunction "EN_3") (pintype "input"))
    )
    (net (code "44") (name "RTC_RST") (class "Default")
      (node (ref "U2") (pin "16") (pinfunction "IO18_16") (pintype "bidirectional"))
      (node (ref "U3") (pin "4") (pinfunction "~{RST}_4") (pintype "input"))
    )
    (net (code "45") (name "RX") (class "Default")
      (node (ref "TP2") (pin "TP") (pinfunction "TP_TP") (pintype "input"))
      (node (ref "U2") (pin "24") (pinfunction "RXD0/GPIO17_24") (pintype "bidirectional"))
    )
    (net (code "46") (name "SCK") (class "Default")
      (node (ref "D10") (pin "2") (pinfunction "2_2") (pintype "passive"))
      (node (ref "J2") (pin "13") (pinfunction "13_13") (pintype "bidirectional"))
      (node (ref "J4") (pin "P5") (pinfunction "CLK_P5") (pintype "bidirectional"))
      (node (ref "R6") (pin "1") (pinfunction "1_1") (pintype "passive"))
      (node (ref "TP8") (pin "TP") (pinfunction "TP_TP") (pintype "input"))
      (node (ref "U1") (pin "6") (pinfunction "CLK_6") (pintype "input"))
      (node (ref "U2") (pin "6") (pinfunction "IO6_6") (pintype "bidirectional"))
    )
    (net (code "47") (name "SCL") (class "Default")
      (node (ref "J3") (pin "4") (pinfunction "4_4") (pintype "passive"))
      (node (ref "R2-PINH") (pin "1") (pinfunction "1_1") (pintype "passive"))
      (node (ref "U10") (pin "4") (pinfunction "SCK_4") (pintype "input"))
      (node (ref "U2") (pin "20") (pinfunction "IO22_20") (pintype "bidirectional"))
      (node (ref "U3") (pin "16") (pinfunction "SCL_16") (pintype "input"))
      (node (ref "U4") (pin "7") (pinfunction "SCL_7") (pintype "input"))
    )
    (net (code "48") (name "SDA") (class "Default")
      (node (ref "J3") (pin "3") (pinfunction "3_3") (pintype "passive"))
      (node (ref "R1-PINH") (pin "1") (pinfunction "1_1") (pintype "passive"))
      (node (ref "U10") (pin "3") (pinfunction "SDI_3") (pintype "bidirectional"))
      (node (ref "U2") (pin "19") (pinfunction "IO21_19") (pintype "bidirectional"))
      (node (ref "U3") (pin "15") (pinfunction "SDA_15") (pintype "bidirectional"))
      (node (ref "U4") (pin "8") (pinfunction "SDA_8") (pintype "bidirectional"))
    )
    (net (code "49") (name "SRC") (class "Default")
      (node (ref "C1") (pin "2") (pinfunction "2_2") (pintype "passive"))
      (node (ref "D5") (pin "1") (pinfunction "K_1") (pintype "bidirectional"))
      (node (ref "L1") (pin "1") (pinfunction "1_1") (pintype "passive"))
      (node (ref "Q3") (pin "3") (pinfunction "D_3") (pintype "bidirectional"))
    )
    (net (code "50") (name "SS_SD") (class "Default")
      (node (ref "D8") (pin "2") (pinfunction "2_2") (pintype "passive"))
      (node (ref "J4") (pin "P2") (pinfunction "CD/DAT3_P2") (pintype "bidirectional"))
      (node (ref "R10") (pin "1") (pinfunction "1_1") (pintype "passive"))
      (node (ref "U2") (pin "4") (pinfunction "IO4_4") (pintype "bidirectional"))
    )
    (net (code "51") (name "TX") (class "Default")
      (node (ref "TP1") (pin "TP") (pinfunction "TP_TP") (pintype "input"))
      (node (ref "U2") (pin "25") (pinfunction "TXD0/GPIO16_25") (pintype "bidirectional"))
    )
    (net (code "52") (name "USB_D+") (class "Default")
      (node (ref "D1") (pin "1") (pinfunction "I/O1_1_1") (pintype "bidirectional"))
      (node (ref "U2") (pin "14") (pinfunction "IO13_14") (pintype "bidirectional"))
    )
    (net (code "53") (name "USB_D-") (class "Default")
      (node (ref "D1") (pin "3") (pinfunction "I/O2_1_3") (pintype "bidirectional"))
      (node (ref "U2") (pin "13") (pinfunction "IO12_13") (pintype "bidirectional"))
    )
    (net (code "54") (name "VBAT") (class "Default")
      (node (ref "C2_BAT") (pin "1") (pinfunction "1_1") (pintype "passive"))
      (node (ref "Q1") (pin "3") (pinfunction "D_3") (pintype "bidirectional"))
      (node (ref "TP3") (pin "TP") (pinfunction "TP_TP") (pintype "input"))
      (node (ref "U4") (pin "2") (pinfunction "CELL_2") (pintype "power_in"))
      (node (ref "U4") (pin "3") (pinfunction "VDD_3") (pintype "power_in"))
      (node (ref "U9") (pin "3") (pinfunction "VBAT_3") (pintype "power_in"))
    )
    (net (code "55") (name "VBUS") (class "Default")
      (node (ref "C1_BAT") (pin "1") (pinfunction "1_1") (pintype "passive"))
      (node (ref "C4_USB") (pin "1") (pinfunction "1_1") (pintype "passive"))
      (node (ref "C5_USB") (pin "1") (pinfunction "1_1") (pintype "passive"))
      (node (ref "CHG_LED") (pin "A") (pinfunction "A_A") (pintype "passive"))
      (node (ref "D1") (pin "5") (pinfunction "VBUS_5") (pintype "bidirectional"))
      (node (ref "D2") (pin "2") (pinfunction "ANODE_2") (pintype "bidirectional"))
      (node (ref "PFMF.050.1") (pin "2") (pinfunction "2_2") (pintype "passive"))
      (node (ref "Q1") (pin "1") (pinfunction "G_1") (pintype "bidirectional"))
      (node (ref "R1_PWRUSB") (pin "2") (pinfunction "2_2") (pintype "passive"))
      (node (ref "TP14") (pin "TP") (pinfunction "TP_TP") (pintype "input"))
      (node (ref "U9") (pin "4") (pinfunction "VIN_4") (pintype "power_in"))
    )
    (net (code "56") (name "VRTC") (class "Default")
      (node (ref "C4") (pin "2") (pinfunction "2_2") (pintype "passive"))
      (node (ref "C8") (pin "1") (pinfunction "1_1") (pintype "passive"))
      (node (ref "R_CAPACITOR") (pin "2") (pinfunction "2_2") (pintype "passive"))
      (node (ref "U3") (pin "14") (pinfunction "VBAT_14") (pintype "power_in"))
    )
    (net (code "57") (name "VUSB") (class "Default")
      (node (ref "J1") (pin "A4") (pinfunction "A4_A4") (pintype "bidirectional"))
      (node (ref "J1") (pin "A9") (pinfunction "A9_A9") (pintype "bidirectional"))
      (node (ref "J1") (pin "B4") (pinfunction "B4_B4") (pintype "bidirectional"))
      (node (ref "J1") (pin "B9") (pinfunction "B9_B9") (pintype "bidirectional"))
      (node (ref "PFMF.050.1") (pin "1") (pinfunction "1_1") (pintype "passive"))
    )
    (net (code "58") (name "unconnected-(IC1-NC-Pad4)") (class "Default")
      (node (ref "IC1") (pin "4") (pinfunction "NC_4") (pintype "no_connect"))
    )
    (net (code "59") (name "unconnected-(IC2-NC-Pad4)") (class "Default")
      (node (ref "IC2") (pin "4") (pinfunction "NC_4") (pintype "no_connect"))
    )
    (net (code "60") (name "unconnected-(J1-PadA8)") (class "Default")
      (node (ref "J1") (pin "A8") (pinfunction "A8_A8") (pintype "bidirectional"))
    )
    (net (code "61") (name "unconnected-(J1-PadB8)") (class "Default")
      (node (ref "J1") (pin "B8") (pinfunction "B8_B8") (pintype "bidirectional"))
    )
    (net (code "62") (name "unconnected-(J1-PadB12)") (class "Default")
      (node (ref "J1") (pin "B12") (pinfunction "B12_B12") (pintype "bidirectional"))
    )
    (net (code "63") (name "unconnected-(J2-Pad1)") (class "Default")
      (node (ref "J2") (pin "1") (pinfunction "1_1") (pintype "bidirectional"))
    )
    (net (code "64") (name "unconnected-(J2-Pad6)") (class "Default")
      (node (ref "J2") (pin "6") (pinfunction "6_6") (pintype "bidirectional"))
    )
    (net (code "65") (name "unconnected-(J2-Pad7)") (class "Default")
      (node (ref "J2") (pin "7") (pinfunction "7_7") (pintype "bidirectional"))
    )
    (net (code "66") (name "unconnected-(J4-DAT1-PadP8)") (class "Default")
      (node (ref "J4") (pin "P8") (pinfunction "DAT1_P8") (pintype "bidirectional"))
    )
    (net (code "67") (name "unconnected-(J4-DAT2-PadP1)") (class "Default")
      (node (ref "J4") (pin "P1") (pinfunction "DAT2_P1") (pintype "bidirectional"))
    )
    (net (code "68") (name "unconnected-(J4-DETECTION_1-PadS1)") (class "Default")
      (node (ref "J4") (pin "S1") (pinfunction "DETECTION_1_S1") (pintype "bidirectional"))
    )
    (net (code "69") (name "unconnected-(J4-DETECTION_2-PadS2)") (class "Default")
      (node (ref "J4") (pin "S2") (pinfunction "DETECTION_2_S2") (pintype "bidirectional"))
    )
    (net (code "70") (name "unconnected-(U2-NC-Pad22)") (class "Default")
      (node (ref "U2") (pin "22") (pinfunction "NC_22") (pintype "no_connect"))
    )
    (net (code "71") (name "unconnected-(U4-~{ALERT}-Pad5)") (class "Default")
      (node (ref "U4") (pin "5") (pinfunction "~{ALERT}_5") (pintype "output"))
    )
  )
)
